# POWER.net
KiCad netlist of a schematic drawn in Altium Designer
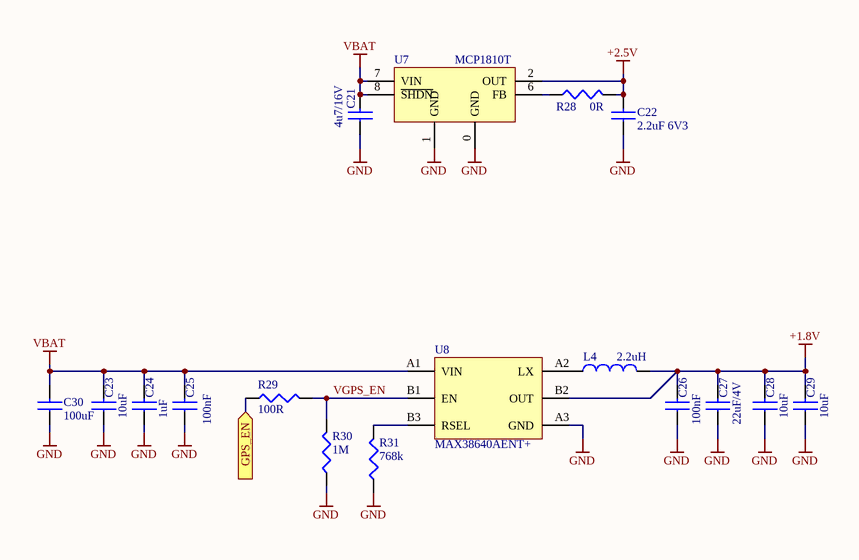
[diagram p0: POWER.SchDoc]

(export (version "E")
  (design (tool "Eeschema 10.0.6"))
  (components
    (comp (ref "C21")
      (value "4u7/16V")
      (footprint "CAP0603")
      (description "MURATA - GRM188R61C475KAAJD - CAP, MLCC, X5R, 4.7UF, 16V, 0603")
      (fields
        (field (name "MANUFACTURER") "MURATA")
        (field (name "MANUFACTURER PART NUMBER") "GRM188R61C475KAAJD")
      )
      (libsource (lib "Passive") (part "C - 4u7  16V 0603"))
    )
    (comp (ref "C22")
      (value "2.2uF 6V3")
      (footprint "CAP0402")
      (description "CAP CER 2.2UF 6.3V 20% X5R 0402")
      (fields
        (field (name "MANUFACTURER") "Murata")
        (field (name "MANUFACTURER PART NUMBER") "GRM155R60J225ME15D")
      )
      (libsource (lib "Passive") (part "C - 2.2uF/6V3/0402"))
    )
    (comp (ref "C23")
      (value "10uF")
      (footprint "CAP0603")
      (description "Cap Ceramic 10uF 10V X5R 10% SMD 0603 85C Paper T/R")
      (fields
        (field (name "MANUFACTURER") "Samsung")
        (field (name "MANUFACTURER PART NUMBER") "CL10A106KP8NNNC")
      )
      (libsource (lib "Passive") (part "C - 10uF/10V"))
    )
    (comp (ref "C24")
      (value "1uF")
      (footprint "CAP0402")
      (description "CAP CER 1UF 10V 20% X5R 0402")
      (fields
        (field (name "MANUFACTURER") "Murata")
        (field (name "MANUFACTURER PART NUMBER") "GRM155R61A105ME15D")
      )
      (libsource (lib "Passive") (part "C - 1uF/0402"))
    )
    (comp (ref "C25")
      (value "100nF")
      (footprint "CAP0402")
      (fields
        (field (name "MANUFACTURER") "Multicomp")
        (field (name "MANUFACTURER PART NUMBER") "MC0402X104J160CT")
        (field (name "TOLERANCE") "5%")
      )
      (libsource (lib "Passive") (part "C - 100nF/0402"))
    )
    (comp (ref "C26")
      (value "100nF")
      (footprint "CAP0402")
      (fields
        (field (name "MANUFACTURER") "Multicomp")
        (field (name "MANUFACTURER PART NUMBER") "MC0402X104J160CT")
        (field (name "TOLERANCE") "5%")
      )
      (libsource (lib "Passive") (part "C - 100nF/0402"))
    )
    (comp (ref "C27")
      (value "22uF/4V")
      (footprint "CAP0603")
      (description "SMD Multilayer Ceramic Capacitor, 22 µF, 4 V, 0603 [1608 Metric], ± 20%, X5R, GRM Series")
      (fields
        (field (name "MANUFACTURER") "Samsung")
        (field (name "MANUFACTURER PART NUMBER") "GRM188R60G226MEA0D")
      )
      (libsource (lib "Passive") (part "C - 10uF/10V"))
    )
    (comp (ref "C28")
      (value "10uF")
      (footprint "CAP0603")
      (description "Cap Ceramic 10uF 10V X5R 10% SMD 0603 85C Paper T/R")
      (fields
        (field (name "MANUFACTURER") "Samsung")
        (field (name "MANUFACTURER PART NUMBER") "CL10A106KP8NNNC")
      )
      (libsource (lib "Passive") (part "C - 10uF/10V"))
    )
    (comp (ref "C29")
      (value "10uF")
      (footprint "CAP0603")
      (description "Cap Ceramic 10uF 10V X5R 10% SMD 0603 85C Paper T/R")
      (fields
        (field (name "MANUFACTURER") "Samsung")
        (field (name "MANUFACTURER PART NUMBER") "CL10A106KP8NNNC")
      )
      (libsource (lib "Passive") (part "C - 10uF/10V"))
    )
    (comp (ref "C30")
      (value "100uF")
      (footprint "CAP0805")
      (description "Multilayer Ceramic Capacitors MLCC - SMD/SMT 0805 100uF 4volts *Derate Voltage/Temp")
      (fields
        (field (name "MANUFACTURER") "Murata")
        (field (name "MANUFACTURER PART NUMBER") "GRM21BR60G107ME15L")
      )
      (libsource (lib "Passive") (part "C - 100uF/0805"))
    )
    (comp (ref "L4")
      (value "2.2uH")
      (footprint "IND2.3X1.7")
      (fields
        (field (name "MANUFACTURER") "Bourns")
        (field (name "MANUFACTURER PART NUMBER") "SRN2009T-2R2M")
        (field (name "IRNAS PART NO.") "/")
      )
      (libsource (lib "Passive") (part "L - 2.2 uH 900mA"))
    )
    (comp (ref "R28")
      (value "0R")
      (footprint "RES0402")
      (description "RESISTOR, 0402, 0R, ANTI SULFURATION")
      (fields
        (field (name "MANUFACTURER") "Multicomp")
        (field (name "MANUFACTURER PART NUMBER") "MCMR04X000PTL")
      )
      (libsource (lib "Passive") (part "R - 0R/0402"))
    )
    (comp (ref "R29")
      (value "100R")
      (footprint "RES0402")
      (fields
        (field (name "MANUFACTURER") "Multicomp")
        (field (name "MANUFACTURER PART NUMBER") "MCMR04X1000FTL")
        (field (name "TOLERANCE") "1%")
      )
      (libsource (lib "Passive") (part "R - 100R/0402"))
    )
    (comp (ref "R30")
      (value "1M")
      (footprint "RES0402")
      (description "MCMR04X1004FTL RES, 1M, 1%, 0.0625W, 0402, THICK FILM")
      (fields
        (field (name "MANUFACTURER") "MULTICOMP")
        (field (name "MANUFACTURER PART NUMBER") "MC0063W060311M")
      )
      (libsource (lib "Passive") (part "R - 1M/0402"))
    )
    (comp (ref "R31")
      (value "768k")
      (footprint "RES0402")
      (description "RESISTOR, 0402, 768k, ANTI SULFURATION")
      (fields
        (field (name "MANUFACTURER") "Multicomp")
        (field (name "MANUFACTURER PART NUMBER") "MCMR04X000PTL")
      )
      (libsource (lib "Passive") (part "R - 768k/0402"))
    )
    (comp (ref "U7")
      (value "MCP1810T")
      (footprint "VDFN_2x2")
      (description "LDO Voltage Regulator, Fixed, 2.5 V to 5.5 V in, 2.5 V/150 mA out, 380 mV drop")
      (fields
        (field (name "MANUFACTURER") "ON SEMICONDUCTOR")
        (field (name "MANUFACTURER PART NUMBER") "LM2596DSADJG")
      )
      (libsource (lib "Active") (part "V_LIN - MCP1810T"))
    )
    (comp (ref "U8")
      (value "MAX38640AENT+")
      (footprint "WLP-6")
      (description "Switching Voltage Regulators Tiny 300nA nanoPower Buck converters in uDFN and WLP pacakges")
      (fields (field (name "MANUFACTURER") "ROHM") (field (name "MANUFACTURER PART NUMBER") "BD70522GUL"))
      (libsource (lib "Active") (part "V_SW - MAX38640AENT+"))
    )
  )
  (nets
    (net (code "1") (name "+1.8V") (class "Default")
      (node (ref "C26") (pin "2") (pinfunction "2_2") (pintype "passive"))
      (node (ref "C27") (pin "2") (pinfunction "2_2") (pintype "passive"))
      (node (ref "C28") (pin "2") (pinfunction "2_2") (pintype "passive"))
      (node (ref "C29") (pin "2") (pinfunction "2_2") (pintype "passive"))
      (node (ref "L4") (pin "2") (pinfunction "2_2") (pintype "passive"))
      (node (ref "U8") (pin "B2") (pinfunction "OUT_B2") (pintype "passive"))
    )
    (net (code "2") (name "+2.5V") (class "Default")
      (node (ref "C22") (pin "2") (pinfunction "2_2") (pintype "passive"))
      (node (ref "R28") (pin "2") (pinfunction "2_2") (pintype "passive"))
      (node (ref "U7") (pin "2") (pinfunction "OUT_2") (pintype "open_collector"))
    )
    (net (code "3") (name "/GPS_EN") (class "Default")
      (node (ref "R29") (pin "1") (pinfunction "1_1") (pintype "passive"))
    )
    (net (code "4") (name "/VGPS_EN") (class "Default")
      (node (ref "R29") (pin "2") (pinfunction "2_2") (pintype "passive"))
      (node (ref "R30") (pin "2") (pinfunction "2_2") (pintype "passive"))
      (node (ref "U8") (pin "B1") (pinfunction "EN_B1") (pintype "passive"))
    )
    (net (code "5") (name "GND") (class "Default")
      (node (ref "C21") (pin "1") (pinfunction "1_1") (pintype "passive"))
      (node (ref "C22") (pin "1") (pinfunction "1_1") (pintype "passive"))
      (node (ref "C23") (pin "1") (pinfunction "1_1") (pintype "passive"))
      (node (ref "C24") (pin "1") (pinfunction "1_1") (pintype "passive"))
      (node (ref "C25") (pin "1") (pinfunction "1_1") (pintype "passive"))
      (node (ref "C26") (pin "1") (pinfunction "1_1") (pintype "passive"))
      (node (ref "C27") (pin "1") (pinfunction "1_1") (pintype "passive"))
      (node (ref "C28") (pin "1") (pinfunction "1_1") (pintype "passive"))
      (node (ref "C29") (pin "1") (pinfunction "1_1") (pintype "passive"))
      (node (ref "C30") (pin "1") (pinfunction "1_1") (pintype "passive"))
      (node (ref "R30") (pin "1") (pinfunction "1_1") (pintype "passive"))
      (node (ref "R31") (pin "1") (pinfunction "1_1") (pintype "passive"))
      (node (ref "U7") (pin "0") (pinfunction "GND_0") (pintype "open_collector"))
      (node (ref "U7") (pin "1") (pinfunction "GND_1") (pintype "open_collector"))
      (node (ref "U8") (pin "A3") (pinfunction "GND_A3") (pintype "passive"))
    )
    (net (code "6") (name "Net-(U7-FB)") (class "Default")
      (node (ref "R28") (pin "1") (pinfunction "1_1") (pintype "passive"))
      (node (ref "U7") (pin "6") (pinfunction "FB_6") (pintype "open_collector"))
    )
    (net (code "7") (name "Net-(U8-LX)") (class "Default")
      (node (ref "L4") (pin "1") (pinfunction "1_1") (pintype "passive"))
      (node (ref "U8") (pin "A2") (pinfunction "LX_A2") (pintype "passive"))
    )
    (net (code "8") (name "Net-(U8-RSEL)") (class "Default")
      (node (ref "R31") (pin "2") (pinfunction "2_2") (pintype "passive"))
      (node (ref "U8") (pin "B3") (pinfunction "RSEL_B3") (pintype "passive"))
    )
    (net (code "9") (name "VBAT") (class "Default")
      (node (ref "C21") (pin "2") (pinfunction "2_2") (pintype "passive"))
      (node (ref "C23") (pin "2") (pinfunction "2_2") (pintype "passive"))
      (node (ref "C24") (pin "2") (pinfunction "2_2") (pintype "passive"))
      (node (ref "C25") (pin "2") (pinfunction "2_2") (pintype "passive"))
      (node (ref "C30") (pin "2") (pinfunction "2_2") (pintype "passive"))
      (node (ref "U7") (pin "7") (pinfunction "VIN_7") (pintype "open_collector"))
      (node (ref "U7") (pin "8") (pinfunction "~{SHDN}_8") (pintype "open_collector"))
      (node (ref "U8") (pin "A1") (pinfunction "VIN_A1") (pintype "passive"))
    )
  )
)
